# VentaConnected_Arduino_V0_01_2017-11-23.net
KiCad netlist of a schematic drawn in EAGLE
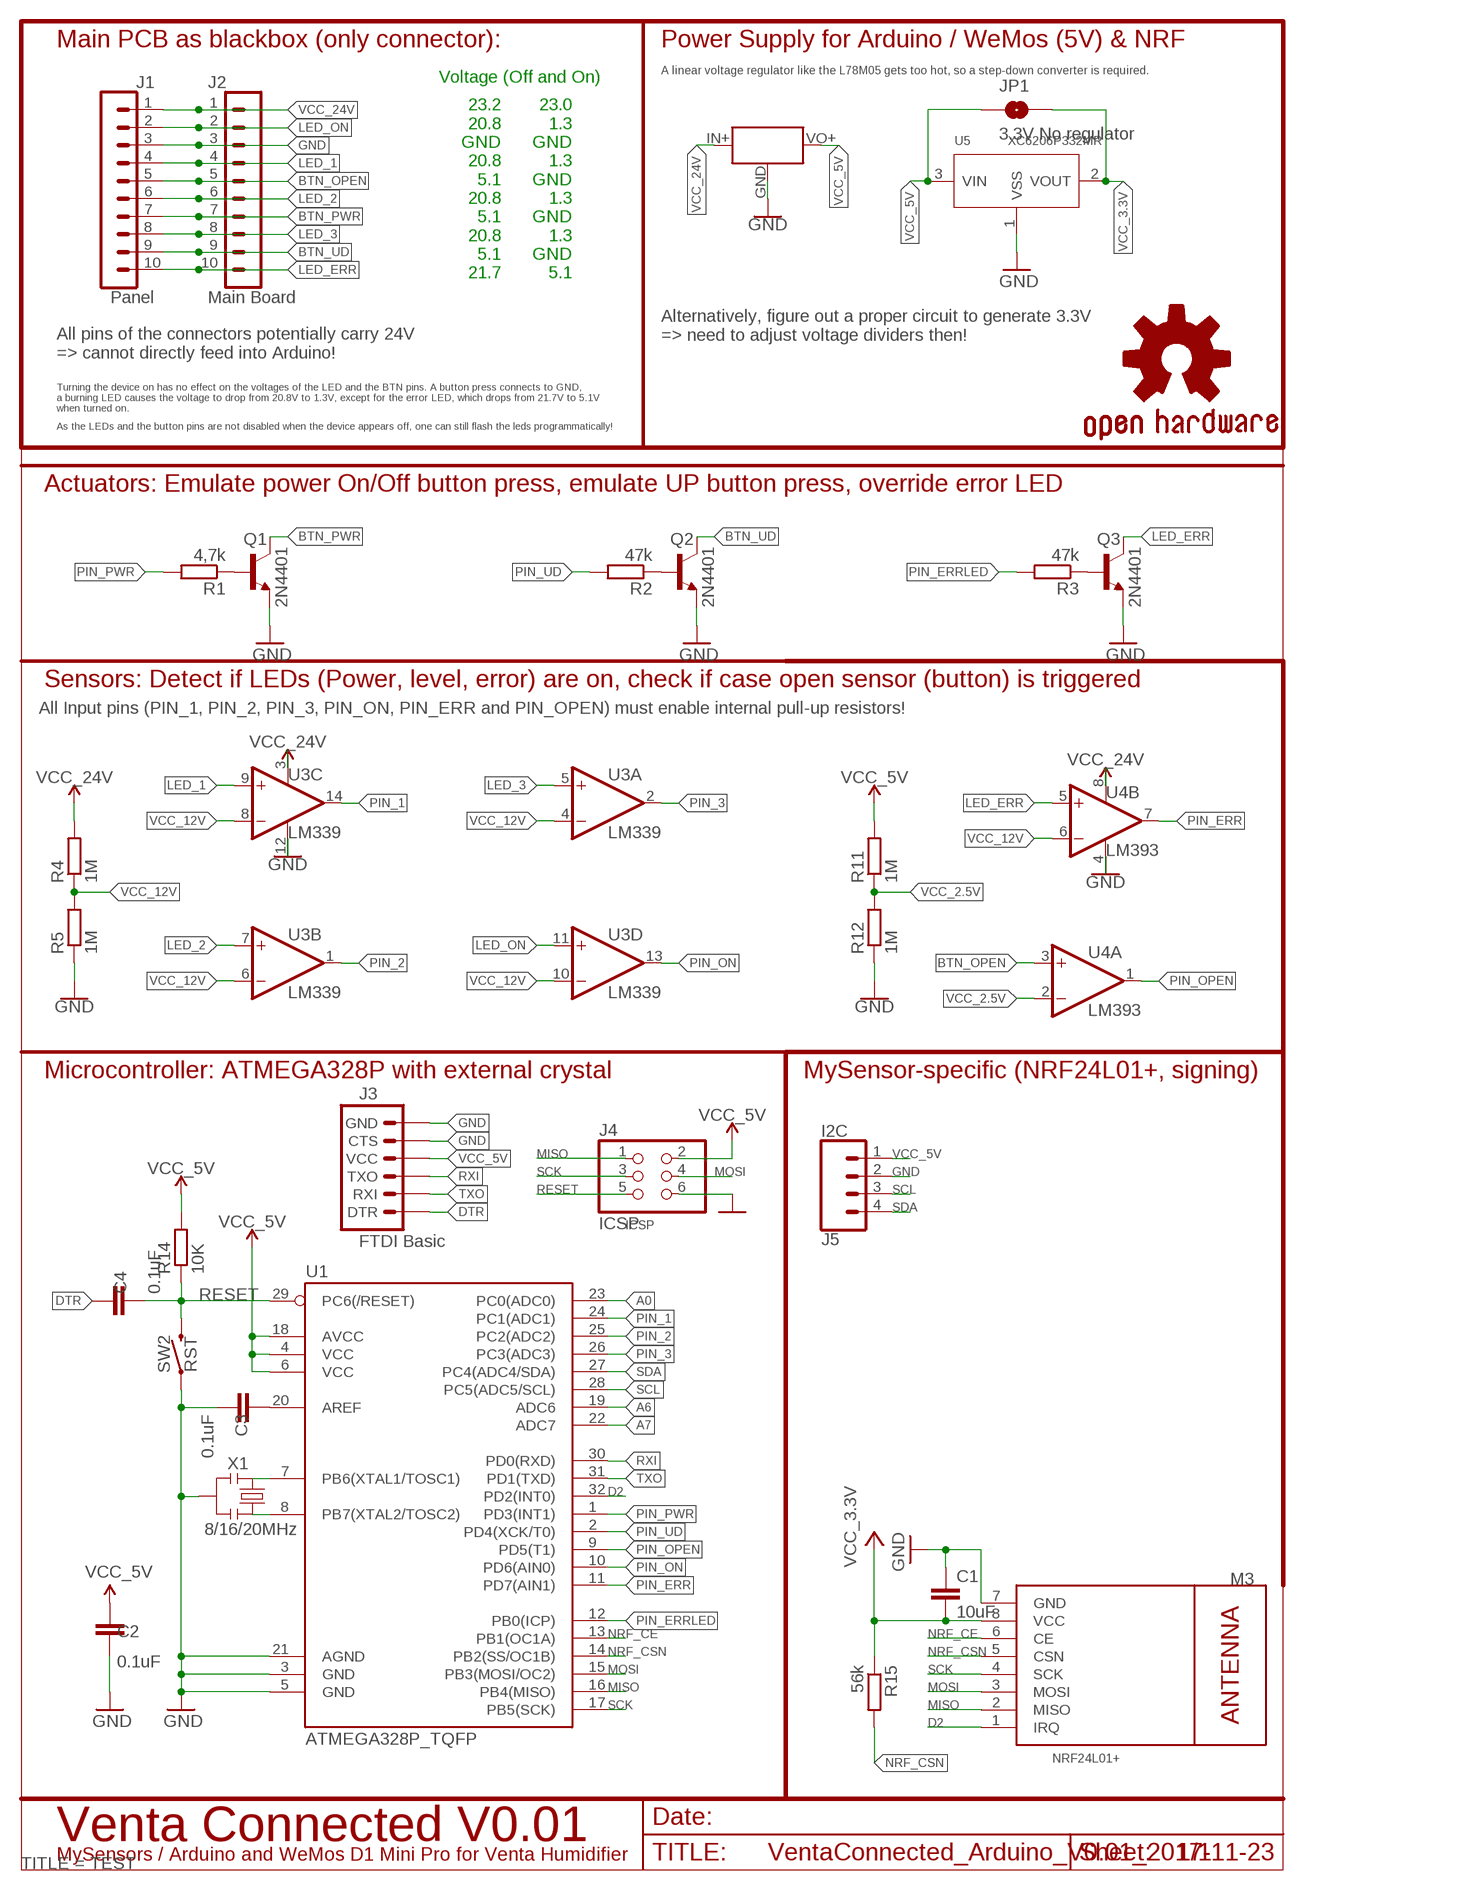
[diagram p0: schematic, sheet 1]

(export (version "E")
  (design (tool "Eeschema 10.0.6"))
  (components
    (comp (ref "C1")
      (value "10uF")
      (footprint "eagle-import:C0805")
      (libsource (lib "eagle-import") (part "C-EUC0805"))
    )
    (comp (ref "C2")
      (value "0.1uF")
      (footprint "eagle-import:C0805")
      (libsource (lib "eagle-import") (part "resistor_348_C-EUC0805"))
    )
    (comp (ref "C3")
      (value "0.1uF")
      (footprint "eagle-import:C0805")
      (libsource (lib "eagle-import") (part "resistor_348_C-EUC0805"))
    )
    (comp (ref "C4")
      (value "0.1uF")
      (footprint "eagle-import:C0805")
      (libsource (lib "eagle-import") (part "resistor_348_C-EUC0805"))
    )
    (comp (ref "GOLD_ORB_SM1")
      (value "OSHWLOGO_GOLD_ORB_SM")
      (footprint "eagle-import:OSHW2")
      (libsource (lib "eagle-import") (part "OSHWLOGO_GOLD_ORB_SM"))
    )
    (comp (ref "J1")
      (value "Panel")
      (footprint "eagle-import:2X5-SHROUDED")
      (libsource (lib "eagle-import") (part "CONN_05X2SHD"))
    )
    (comp (ref "J2")
      (value "Main Board")
      (footprint "eagle-import:2X5")
      (libsource (lib "eagle-import") (part "CONN_05X2PTH"))
    )
    (comp (ref "J3")
      (value "FTDI Basic")
      (footprint "eagle-import:1X06")
      (libsource (lib "eagle-import") (part "ARDUINO_SERIAL_PROGRAMPTH"))
    )
    (comp (ref "J4")
      (value "ICSP")
      (footprint "eagle-import:2X03")
      (libsource (lib "eagle-import") (part "PINHD-2X3"))
    )
    (comp (ref "J5")
      (value "I2C")
      (footprint "eagle-import:1X04")
      (libsource (lib "eagle-import") (part "CONN_04"))
    )
    (comp (ref "JP1")
      (value "3.3V No regulator")
      (footprint "eagle-import:SMT-JUMPER_2_NO_SILK")
      (libsource (lib "eagle-import") (part "JUMPER-SMT_2_NO_SILK"))
    )
    (comp (ref "M3")
      (value "NRF24L01+")
      (footprint "eagle-import:WIRELESS-NRF24L01-SMD")
      (libsource (lib "eagle-import") (part "WIRELESS-NRF24L01SMD"))
    )
    (comp (ref "Q1")
      (value "2N4401")
      (footprint "eagle-import:SOT23-BEC")
      (libsource (lib "eagle-import") (part "-NPN-SOT23-BECMMBT4401LT1"))
    )
    (comp (ref "Q2")
      (value "2N4401")
      (footprint "eagle-import:SOT23-BEC")
      (libsource (lib "eagle-import") (part "-NPN-SOT23-BECMMBT4401LT1"))
    )
    (comp (ref "Q3")
      (value "2N4401")
      (footprint "eagle-import:SOT23-BEC")
      (libsource (lib "eagle-import") (part "-NPN-SOT23-BECMMBT4401LT1"))
    )
    (comp (ref "R1")
      (value "4,7k")
      (footprint "eagle-import:R0805")
      (libsource (lib "eagle-import") (part "resistor_348_R-EU_R0805"))
    )
    (comp (ref "R2")
      (value "47k")
      (footprint "eagle-import:R0805")
      (libsource (lib "eagle-import") (part "resistor_348_R-EU_R0805"))
    )
    (comp (ref "R3")
      (value "47k")
      (footprint "eagle-import:R0805")
      (libsource (lib "eagle-import") (part "resistor_348_R-EU_R0805"))
    )
    (comp (ref "R4")
      (value "1M")
      (footprint "eagle-import:R0805")
      (libsource (lib "eagle-import") (part "resistor_348_R-EU_R0805"))
    )
    (comp (ref "R5")
      (value "1M")
      (footprint "eagle-import:R0805")
      (libsource (lib "eagle-import") (part "resistor_348_R-EU_R0805"))
    )
    (comp (ref "R11")
      (value "1M")
      (footprint "eagle-import:R0805")
      (libsource (lib "eagle-import") (part "resistor_348_R-EU_R0805"))
    )
    (comp (ref "R12")
      (value "1M")
      (footprint "eagle-import:R0805")
      (libsource (lib "eagle-import") (part "resistor_348_R-EU_R0805"))
    )
    (comp (ref "R14")
      (value "10K")
      (footprint "eagle-import:R0805")
      (libsource (lib "eagle-import") (part "rcl_334_R-EU_R0805"))
    )
    (comp (ref "R15")
      (value "56k")
      (footprint "eagle-import:R0805")
      (libsource (lib "eagle-import") (part "R-EU_R0805"))
    )
    (comp (ref "SW2")
      (value "RST")
      (footprint "eagle-import:TACTILE_SWITCH_SMD_6.0X3.5MM")
      (libsource (lib "eagle-import") (part "MOMENTARY-SWITCH-SPST-SMD-6.0X3.5MM"))
    )
    (comp (ref "U1")
      (value "ATMEGA328P_TQFP")
      (footprint "eagle-import:TQFP32-08")
      (libsource (lib "eagle-import") (part "ATMEGA328P_TQFP"))
    )
    (comp (ref "U2")
      (value "MINI_BUCK_CONVERTER_UPSIDEDOWN")
      (footprint "eagle-import:MINI_BUCK_CONVERTER_UPDOWN")
      (libsource (lib "eagle-import") (part "MINI_BUCK_CONVERTER_UPSIDEDOWN"))
    )
    (comp (ref "U3")
      (value "LM339")
      (footprint "eagle-import:SO14")
      (libsource (lib "eagle-import") (part "TLC339D"))
    )
    (comp (ref "U4")
      (value "LM393")
      (footprint "eagle-import:SO08")
      (libsource (lib "eagle-import") (part "LM393D"))
    )
    (comp (ref "U5")
      (value "XC6206P332MR")
      (footprint "eagle-import:SOT-23")
      (fields (field (name "MPN") "XC6206P332MR-G"))
      (libsource (lib "eagle-import") (part "PMIC-LDO-XC6206P332MR-G(SOT23)"))
    )
    (comp (ref "X1")
      (value "8/16/20MHz")
      (footprint "eagle-import:RESONATOR-SMD-1_1")
      (libsource (lib "eagle-import") (part "RESONATOR1{colon}1"))
    )
  )
  (nets
    (net (code "1") (name "/D2") (class "Default")
      (node (ref "M3") (pin "1") (pinfunction "IRQ_1") (pintype "bidirectional"))
      (node (ref "U1") (pin "32") (pinfunction "PD2(INT0)_32") (pintype "bidirectional"))
    )
    (net (code "2") (name "/MISO") (class "Default")
      (node (ref "J4") (pin "1") (pinfunction "1_1") (pintype "passive"))
      (node (ref "M3") (pin "2") (pinfunction "MISO_2") (pintype "bidirectional"))
      (node (ref "U1") (pin "16") (pinfunction "PB4(MISO)_16") (pintype "bidirectional"))
    )
    (net (code "3") (name "/MOSI") (class "Default")
      (node (ref "J4") (pin "4") (pinfunction "4_4") (pintype "passive"))
      (node (ref "M3") (pin "3") (pinfunction "MOSI_3") (pintype "bidirectional"))
      (node (ref "U1") (pin "15") (pinfunction "PB3(MOSI/OC2)_15") (pintype "bidirectional"))
    )
    (net (code "4") (name "/NRF_CE") (class "Default")
      (node (ref "M3") (pin "6") (pinfunction "CE_6") (pintype "bidirectional"))
      (node (ref "U1") (pin "13") (pinfunction "PB1(OC1A)_13") (pintype "bidirectional"))
    )
    (net (code "5") (name "/RESET") (class "Default")
      (node (ref "C4") (pin "1") (pinfunction "1_1") (pintype "passive"))
      (node (ref "J4") (pin "5") (pinfunction "5_5") (pintype "passive"))
      (node (ref "R14") (pin "1") (pinfunction "1_1") (pintype "passive"))
      (node (ref "SW2") (pin "2") (pinfunction "2_2") (pintype "passive"))
      (node (ref "U1") (pin "29") (pinfunction "PC6(/RESET)_29") (pintype "bidirectional"))
    )
    (net (code "6") (name "/SCK") (class "Default")
      (node (ref "J4") (pin "3") (pinfunction "3_3") (pintype "passive"))
      (node (ref "M3") (pin "4") (pinfunction "SCK_4") (pintype "bidirectional"))
      (node (ref "U1") (pin "17") (pinfunction "PB5(SCK)_17") (pintype "bidirectional"))
    )
    (net (code "7") (name "A0") (class "Default")
      (node (ref "U1") (pin "23") (pinfunction "PC0(ADC0)_23") (pintype "bidirectional"))
    )
    (net (code "8") (name "A6") (class "Default")
      (node (ref "U1") (pin "19") (pinfunction "ADC6_19") (pintype "bidirectional"))
    )
    (net (code "9") (name "A7") (class "Default")
      (node (ref "U1") (pin "22") (pinfunction "ADC7_22") (pintype "bidirectional"))
    )
    (net (code "10") (name "BTN_OPEN") (class "Default")
      (node (ref "J1") (pin "5") (pinfunction "5_5") (pintype "passive"))
      (node (ref "J2") (pin "5") (pinfunction "5_5") (pintype "passive"))
      (node (ref "U4") (pin "3") (pinfunction "+IN_3") (pintype "input"))
    )
    (net (code "11") (name "BTN_PWR") (class "Default")
      (node (ref "J1") (pin "7") (pinfunction "7_7") (pintype "passive"))
      (node (ref "J2") (pin "7") (pinfunction "7_7") (pintype "passive"))
      (node (ref "Q1") (pin "C") (pinfunction "C_C") (pintype "passive"))
    )
    (net (code "12") (name "BTN_UD") (class "Default")
      (node (ref "J1") (pin "9") (pinfunction "9_9") (pintype "passive"))
      (node (ref "J2") (pin "9") (pinfunction "9_9") (pintype "passive"))
      (node (ref "Q2") (pin "C") (pinfunction "C_C") (pintype "passive"))
    )
    (net (code "13") (name "DTR") (class "Default")
      (node (ref "C4") (pin "2") (pinfunction "2_2") (pintype "passive"))
      (node (ref "J3") (pin "1") (pinfunction "DTR_1") (pintype "passive"))
    )
    (net (code "14") (name "GND") (class "Default")
      (node (ref "C1") (pin "1") (pinfunction "1_1") (pintype "passive"))
      (node (ref "C2") (pin "1") (pinfunction "1_1") (pintype "passive"))
      (node (ref "C3") (pin "1") (pinfunction "1_1") (pintype "passive"))
      (node (ref "J1") (pin "3") (pinfunction "3_3") (pintype "passive"))
      (node (ref "J2") (pin "3") (pinfunction "3_3") (pintype "passive"))
      (node (ref "J3") (pin "5") (pinfunction "CTS_5") (pintype "passive"))
      (node (ref "J3") (pin "6") (pinfunction "GND_6") (pintype "passive"))
      (node (ref "J4") (pin "6") (pinfunction "6_6") (pintype "passive"))
      (node (ref "J5") (pin "2") (pinfunction "2_2") (pintype "passive"))
      (node (ref "M3") (pin "7") (pinfunction "GND_7") (pintype "power_in"))
      (node (ref "Q1") (pin "E") (pinfunction "E_E") (pintype "passive"))
      (node (ref "Q2") (pin "E") (pinfunction "E_E") (pintype "passive"))
      (node (ref "Q3") (pin "E") (pinfunction "E_E") (pintype "passive"))
      (node (ref "R12") (pin "1") (pinfunction "1_1") (pintype "passive"))
      (node (ref "R5") (pin "1") (pinfunction "1_1") (pintype "passive"))
      (node (ref "SW2") (pin "1") (pinfunction "1_1") (pintype "passive"))
      (node (ref "U1") (pin "21") (pinfunction "AGND_21") (pintype "bidirectional"))
      (node (ref "U1") (pin "3") (pinfunction "GND_3") (pintype "bidirectional"))
      (node (ref "U1") (pin "5") (pinfunction "GND_5") (pintype "bidirectional"))
      (node (ref "U2") (pin "GND") (pinfunction "GND_GND") (pintype "bidirectional"))
      (node (ref "U3") (pin "12") (pinfunction "V-_12") (pintype "power_in"))
      (node (ref "U4") (pin "4") (pinfunction "V-_4") (pintype "power_in"))
      (node (ref "U5") (pin "1") (pinfunction "VSS_1") (pintype "power_in"))
      (node (ref "X1") (pin "2") (pinfunction "2_2") (pintype "passive"))
    )
    (net (code "15") (name "LED_1") (class "Default")
      (node (ref "J1") (pin "4") (pinfunction "4_4") (pintype "passive"))
      (node (ref "J2") (pin "4") (pinfunction "4_4") (pintype "passive"))
      (node (ref "U3") (pin "9") (pinfunction "+IN_9") (pintype "input"))
    )
    (net (code "16") (name "LED_2") (class "Default")
      (node (ref "J1") (pin "6") (pinfunction "6_6") (pintype "passive"))
      (node (ref "J2") (pin "6") (pinfunction "6_6") (pintype "passive"))
      (node (ref "U3") (pin "7") (pinfunction "+IN_7") (pintype "input"))
    )
    (net (code "17") (name "LED_3") (class "Default")
      (node (ref "J1") (pin "8") (pinfunction "8_8") (pintype "passive"))
      (node (ref "J2") (pin "8") (pinfunction "8_8") (pintype "passive"))
      (node (ref "U3") (pin "5") (pinfunction "+IN_5") (pintype "input"))
    )
    (net (code "18") (name "LED_ERR") (class "Default")
      (node (ref "J1") (pin "10") (pinfunction "10_10") (pintype "passive"))
      (node (ref "J2") (pin "10") (pinfunction "10_10") (pintype "passive"))
      (node (ref "Q3") (pin "C") (pinfunction "C_C") (pintype "passive"))
      (node (ref "U4") (pin "5") (pinfunction "+IN_5") (pintype "input"))
    )
    (net (code "19") (name "LED_ON") (class "Default")
      (node (ref "J1") (pin "2") (pinfunction "2_2") (pintype "passive"))
      (node (ref "J2") (pin "2") (pinfunction "2_2") (pintype "passive"))
      (node (ref "U3") (pin "11") (pinfunction "+IN_11") (pintype "input"))
    )
    (net (code "20") (name "NRF_CSN") (class "Default")
      (node (ref "M3") (pin "5") (pinfunction "CSN_5") (pintype "bidirectional"))
      (node (ref "R15") (pin "2") (pinfunction "2_2") (pintype "passive"))
      (node (ref "U1") (pin "14") (pinfunction "PB2(SS/OC1B)_14") (pintype "bidirectional"))
    )
    (net (code "21") (name "Net-(Q1-PadB)") (class "Default")
      (node (ref "Q1") (pin "B") (pinfunction "B_B") (pintype "passive"))
      (node (ref "R1") (pin "1") (pinfunction "1_1") (pintype "passive"))
    )
    (net (code "22") (name "Net-(Q2-PadB)") (class "Default")
      (node (ref "Q2") (pin "B") (pinfunction "B_B") (pintype "passive"))
      (node (ref "R2") (pin "1") (pinfunction "1_1") (pintype "passive"))
    )
    (net (code "23") (name "Net-(Q3-PadB)") (class "Default")
      (node (ref "Q3") (pin "B") (pinfunction "B_B") (pintype "passive"))
      (node (ref "R3") (pin "1") (pinfunction "1_1") (pintype "passive"))
    )
    (net (code "24") (name "Net-(U1-AREF)") (class "Default")
      (node (ref "C3") (pin "2") (pinfunction "2_2") (pintype "passive"))
      (node (ref "U1") (pin "20") (pinfunction "AREF_20") (pintype "bidirectional"))
    )
    (net (code "25") (name "Net-(U1-PB6(XTAL1{slash}TOSC1))") (class "Default")
      (node (ref "U1") (pin "7") (pinfunction "PB6(XTAL1/TOSC1)_7") (pintype "bidirectional"))
      (node (ref "X1") (pin "1") (pinfunction "1_1") (pintype "passive"))
    )
    (net (code "26") (name "Net-(U1-PB7(XTAL2{slash}TOSC2))") (class "Default")
      (node (ref "U1") (pin "8") (pinfunction "PB7(XTAL2/TOSC2)_8") (pintype "bidirectional"))
      (node (ref "X1") (pin "3") (pinfunction "3_3") (pintype "passive"))
    )
    (net (code "27") (name "PIN_1") (class "Default")
      (node (ref "U1") (pin "24") (pinfunction "PC1(ADC1)_24") (pintype "bidirectional"))
      (node (ref "U3") (pin "14") (pinfunction "OUT_14") (pintype "output"))
    )
    (net (code "28") (name "PIN_2") (class "Default")
      (node (ref "U1") (pin "25") (pinfunction "PC2(ADC2)_25") (pintype "bidirectional"))
      (node (ref "U3") (pin "1") (pinfunction "OUT_1") (pintype "output"))
    )
    (net (code "29") (name "PIN_3") (class "Default")
      (node (ref "U1") (pin "26") (pinfunction "PC3(ADC3)_26") (pintype "bidirectional"))
      (node (ref "U3") (pin "2") (pinfunction "OUT_2") (pintype "output"))
    )
    (net (code "30") (name "PIN_ERR") (class "Default")
      (node (ref "U1") (pin "11") (pinfunction "PD7(AIN1)_11") (pintype "bidirectional"))
      (node (ref "U4") (pin "7") (pinfunction "OUT_7") (pintype "output"))
    )
    (net (code "31") (name "PIN_ERRLED") (class "Default")
      (node (ref "R3") (pin "2") (pinfunction "2_2") (pintype "passive"))
      (node (ref "U1") (pin "12") (pinfunction "PB0(ICP)_12") (pintype "bidirectional"))
    )
    (net (code "32") (name "PIN_ON") (class "Default")
      (node (ref "U1") (pin "10") (pinfunction "PD6(AIN0)_10") (pintype "bidirectional"))
      (node (ref "U3") (pin "13") (pinfunction "OUT_13") (pintype "output"))
    )
    (net (code "33") (name "PIN_OPEN") (class "Default")
      (node (ref "U1") (pin "9") (pinfunction "PD5(T1)_9") (pintype "bidirectional"))
      (node (ref "U4") (pin "1") (pinfunction "OUT_1") (pintype "output"))
    )
    (net (code "34") (name "PIN_PWR") (class "Default")
      (node (ref "R1") (pin "2") (pinfunction "2_2") (pintype "passive"))
      (node (ref "U1") (pin "1") (pinfunction "PD3(INT1)_1") (pintype "bidirectional"))
    )
    (net (code "35") (name "PIN_UD") (class "Default")
      (node (ref "R2") (pin "2") (pinfunction "2_2") (pintype "passive"))
      (node (ref "U1") (pin "2") (pinfunction "PD4(XCK/T0)_2") (pintype "bidirectional"))
    )
    (net (code "36") (name "RXI") (class "Default")
      (node (ref "J3") (pin "3") (pinfunction "TXO_3") (pintype "passive"))
      (node (ref "U1") (pin "30") (pinfunction "PD0(RXD)_30") (pintype "bidirectional"))
    )
    (net (code "37") (name "SCL") (class "Default")
      (node (ref "J5") (pin "3") (pinfunction "3_3") (pintype "passive"))
      (node (ref "U1") (pin "28") (pinfunction "PC5(ADC5/SCL)_28") (pintype "bidirectional"))
    )
    (net (code "38") (name "SDA") (class "Default")
      (node (ref "J5") (pin "4") (pinfunction "4_4") (pintype "passive"))
      (node (ref "U1") (pin "27") (pinfunction "PC4(ADC4/SDA)_27") (pintype "bidirectional"))
    )
    (net (code "39") (name "TXO") (class "Default")
      (node (ref "J3") (pin "2") (pinfunction "RXI_2") (pintype "passive"))
      (node (ref "U1") (pin "31") (pinfunction "PD1(TXD)_31") (pintype "bidirectional"))
    )
    (net (code "40") (name "VCC_2.5V") (class "Default")
      (node (ref "R11") (pin "1") (pinfunction "1_1") (pintype "passive"))
      (node (ref "R12") (pin "2") (pinfunction "2_2") (pintype "passive"))
      (node (ref "U4") (pin "2") (pinfunction "-IN_2") (pintype "input"))
    )
    (net (code "41") (name "VCC_3.3V") (class "Default")
      (node (ref "C1") (pin "2") (pinfunction "2_2") (pintype "passive"))
      (node (ref "JP1") (pin "2") (pinfunction "2_2") (pintype "passive"))
      (node (ref "M3") (pin "8") (pinfunction "VCC_8") (pintype "power_in"))
      (node (ref "R15") (pin "1") (pinfunction "1_1") (pintype "passive"))
      (node (ref "U5") (pin "2") (pinfunction "VOUT_2") (pintype "output"))
    )
    (net (code "42") (name "VCC_5V") (class "Default")
      (node (ref "C2") (pin "2") (pinfunction "2_2") (pintype "passive"))
      (node (ref "J3") (pin "4") (pinfunction "VCC_4") (pintype "passive"))
      (node (ref "J4") (pin "2") (pinfunction "2_2") (pintype "passive"))
      (node (ref "J5") (pin "1") (pinfunction "1_1") (pintype "passive"))
      (node (ref "JP1") (pin "1") (pinfunction "1_1") (pintype "passive"))
      (node (ref "R11") (pin "2") (pinfunction "2_2") (pintype "passive"))
      (node (ref "R14") (pin "2") (pinfunction "2_2") (pintype "passive"))
      (node (ref "U1") (pin "18") (pinfunction "AVCC_18") (pintype "bidirectional"))
      (node (ref "U1") (pin "4") (pinfunction "VCC_4") (pintype "bidirectional"))
      (node (ref "U1") (pin "6") (pinfunction "VCC_6") (pintype "bidirectional"))
      (node (ref "U2") (pin "VO+") (pinfunction "VOUT_VO+") (pintype "power_in"))
      (node (ref "U5") (pin "3") (pinfunction "VIN_3") (pintype "input"))
    )
    (net (code "43") (name "VCC_12V") (class "Default")
      (node (ref "R4") (pin "1") (pinfunction "1_1") (pintype "passive"))
      (node (ref "R5") (pin "2") (pinfunction "2_2") (pintype "passive"))
      (node (ref "U3") (pin "10") (pinfunction "-IN_10") (pintype "input"))
      (node (ref "U3") (pin "4") (pinfunction "-IN_4") (pintype "input"))
      (node (ref "U3") (pin "6") (pinfunction "-IN_6") (pintype "input"))
      (node (ref "U3") (pin "8") (pinfunction "-IN_8") (pintype "input"))
      (node (ref "U4") (pin "6") (pinfunction "-IN_6") (pintype "input"))
    )
    (net (code "44") (name "VCC_24V") (class "Default")
      (node (ref "J1") (pin "1") (pinfunction "1_1") (pintype "passive"))
      (node (ref "J2") (pin "1") (pinfunction "1_1") (pintype "passive"))
      (node (ref "R4") (pin "2") (pinfunction "2_2") (pintype "passive"))
      (node (ref "U2") (pin "IN+") (pinfunction "VIN_IN+") (pintype "input"))
      (node (ref "U3") (pin "3") (pinfunction "V+_3") (pintype "power_in"))
      (node (ref "U4") (pin "8") (pinfunction "V+_8") (pintype "power_in"))
    )
  )
)
